# deneme.net
KiCad netlist of a schematic drawn in EAGLE
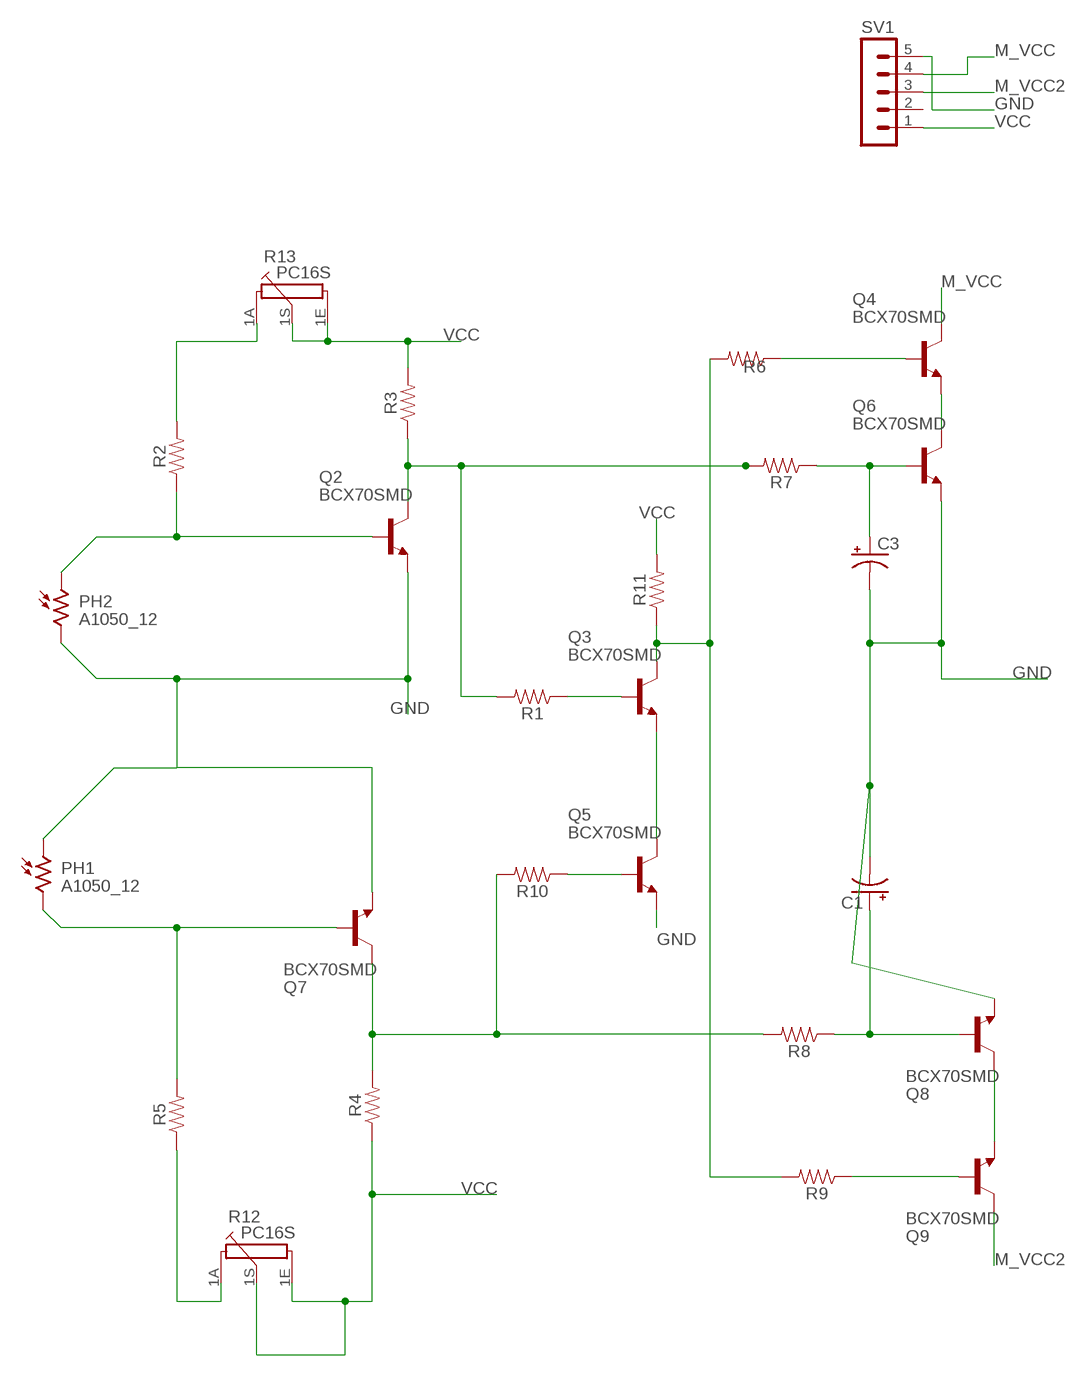
[diagram p0: schematic, sheet 1]

(export (version "E")
  (design (tool "Eeschema 10.0.6"))
  (components
    (comp (ref "C1")
      (value "CPOL-USUD-6,3X7,7")
      (footprint "eagle-import:UD-6,3X7,7_NICHICON")
      (libsource (lib "eagle-import") (part "CPOL-USUD-6,3X7,7"))
    )
    (comp (ref "C3")
      (value "CPOL-USUD-6,3X7,7")
      (footprint "eagle-import:UD-6,3X7,7_NICHICON")
      (libsource (lib "eagle-import") (part "CPOL-USUD-6,3X7,7"))
    )
    (comp (ref "PH1")
      (value "A1050_12")
      (footprint "eagle-import:T0-46-A10XX")
      (libsource (lib "eagle-import") (part "A1050_12"))
    )
    (comp (ref "PH2")
      (value "A1050_12")
      (footprint "eagle-import:T0-46-A10XX")
      (libsource (lib "eagle-import") (part "A1050_12"))
    )
    (comp (ref "Q2")
      (value "BCX70SMD")
      (footprint "eagle-import:SOT23")
      (libsource (lib "eagle-import") (part "BCX70SMD"))
    )
    (comp (ref "Q3")
      (value "BCX70SMD")
      (footprint "eagle-import:SOT23")
      (libsource (lib "eagle-import") (part "BCX70SMD"))
    )
    (comp (ref "Q4")
      (value "BCX70SMD")
      (footprint "eagle-import:SOT23")
      (libsource (lib "eagle-import") (part "BCX70SMD"))
    )
    (comp (ref "Q5")
      (value "BCX70SMD")
      (footprint "eagle-import:SOT23")
      (libsource (lib "eagle-import") (part "BCX70SMD"))
    )
    (comp (ref "Q6")
      (value "BCX70SMD")
      (footprint "eagle-import:SOT23")
      (libsource (lib "eagle-import") (part "BCX70SMD"))
    )
    (comp (ref "Q7")
      (value "BCX70SMD")
      (footprint "eagle-import:SOT23")
      (libsource (lib "eagle-import") (part "BCX70SMD"))
    )
    (comp (ref "Q8")
      (value "BCX70SMD")
      (footprint "eagle-import:SOT23")
      (libsource (lib "eagle-import") (part "BCX70SMD"))
    )
    (comp (ref "Q9")
      (value "BCX70SMD")
      (footprint "eagle-import:SOT23")
      (libsource (lib "eagle-import") (part "BCX70SMD"))
    )
    (comp (ref "R1")
      (value "RESISTOR0805")
      (footprint "eagle-import:0805")
      (libsource (lib "eagle-import") (part "RESISTOR0805"))
    )
    (comp (ref "R2")
      (value "RESISTOR0805")
      (footprint "eagle-import:0805")
      (libsource (lib "eagle-import") (part "RESISTOR0805"))
    )
    (comp (ref "R3")
      (value "RESISTOR0805")
      (footprint "eagle-import:0805")
      (libsource (lib "eagle-import") (part "RESISTOR0805"))
    )
    (comp (ref "R4")
      (value "RESISTOR0805")
      (footprint "eagle-import:0805")
      (libsource (lib "eagle-import") (part "RESISTOR0805"))
    )
    (comp (ref "R5")
      (value "RESISTOR0805")
      (footprint "eagle-import:0805")
      (libsource (lib "eagle-import") (part "RESISTOR0805"))
    )
    (comp (ref "R6")
      (value "RESISTOR0805")
      (footprint "eagle-import:0805")
      (libsource (lib "eagle-import") (part "RESISTOR0805"))
    )
    (comp (ref "R7")
      (value "RESISTOR0805")
      (footprint "eagle-import:0805")
      (libsource (lib "eagle-import") (part "RESISTOR0805"))
    )
    (comp (ref "R8")
      (value "RESISTOR0805")
      (footprint "eagle-import:0805")
      (libsource (lib "eagle-import") (part "RESISTOR0805"))
    )
    (comp (ref "R9")
      (value "RESISTOR0805")
      (footprint "eagle-import:0805")
      (libsource (lib "eagle-import") (part "RESISTOR0805"))
    )
    (comp (ref "R10")
      (value "RESISTOR0805")
      (footprint "eagle-import:0805")
      (libsource (lib "eagle-import") (part "RESISTOR0805"))
    )
    (comp (ref "R11")
      (value "RESISTOR0805")
      (footprint "eagle-import:0805")
      (libsource (lib "eagle-import") (part "RESISTOR0805"))
    )
    (comp (ref "R12")
      (value "PC16S")
      (footprint "eagle-import:PC16S")
      (libsource (lib "eagle-import") (part "PC16S"))
    )
    (comp (ref "R13")
      (value "PC16S")
      (footprint "eagle-import:PC16S")
      (libsource (lib "eagle-import") (part "PC16S"))
    )
    (comp (ref "SV1")
      (value "MA05-1")
      (footprint "eagle-import:MA05-1")
      (libsource (lib "eagle-import") (part "MA05-1"))
    )
  )
  (nets
    (net (code "1") (name "/GND") (class "Default")
      (node (ref "C1") (pin "-") (pinfunction "-_-") (pintype "passive"))
      (node (ref "C3") (pin "-") (pinfunction "-_-") (pintype "passive"))
      (node (ref "PH1") (pin "1") (pinfunction "1_1") (pintype "passive"))
      (node (ref "PH2") (pin "2") (pinfunction "2_2") (pintype "passive"))
      (node (ref "Q2") (pin "2") (pinfunction "E_2") (pintype "passive"))
      (node (ref "Q5") (pin "2") (pinfunction "E_2") (pintype "passive"))
      (node (ref "Q6") (pin "2") (pinfunction "E_2") (pintype "passive"))
      (node (ref "Q7") (pin "2") (pinfunction "E_2") (pintype "passive"))
      (node (ref "Q8") (pin "2") (pinfunction "E_2") (pintype "passive"))
      (node (ref "SV1") (pin "5") (pinfunction "5_5") (pintype "passive"))
    )
    (net (code "2") (name "/M_VCC") (class "Default")
      (node (ref "Q4") (pin "3") (pinfunction "C_3") (pintype "passive"))
      (node (ref "SV1") (pin "4") (pinfunction "4_4") (pintype "passive"))
    )
    (net (code "3") (name "/M_VCC2") (class "Default")
      (node (ref "Q9") (pin "3") (pinfunction "C_3") (pintype "passive"))
      (node (ref "SV1") (pin "3") (pinfunction "3_3") (pintype "passive"))
    )
    (net (code "4") (name "/VCC") (class "Default")
      (node (ref "R11") (pin "2") (pinfunction "2_2") (pintype "passive"))
      (node (ref "R12") (pin "1E") (pinfunction "1E_1E") (pintype "passive"))
      (node (ref "R12") (pin "1S") (pinfunction "1S_1S") (pintype "passive"))
      (node (ref "R13") (pin "1E") (pinfunction "1E_1E") (pintype "passive"))
      (node (ref "R13") (pin "1S") (pinfunction "1S_1S") (pintype "passive"))
      (node (ref "R3") (pin "2") (pinfunction "2_2") (pintype "passive"))
      (node (ref "R4") (pin "1") (pinfunction "1_1") (pintype "passive"))
      (node (ref "SV1") (pin "1") (pinfunction "1_1") (pintype "passive"))
    )
    (net (code "5") (name "Net-(Q2-B)") (class "Default")
      (node (ref "PH2") (pin "1") (pinfunction "1_1") (pintype "passive"))
      (node (ref "Q2") (pin "1") (pinfunction "B_1") (pintype "passive"))
      (node (ref "R2") (pin "1") (pinfunction "1_1") (pintype "passive"))
    )
    (net (code "6") (name "Net-(Q2-C)") (class "Default")
      (node (ref "Q2") (pin "3") (pinfunction "C_3") (pintype "passive"))
      (node (ref "R1") (pin "2") (pinfunction "2_2") (pintype "passive"))
      (node (ref "R3") (pin "1") (pinfunction "1_1") (pintype "passive"))
      (node (ref "R7") (pin "2") (pinfunction "2_2") (pintype "passive"))
    )
    (net (code "7") (name "Net-(Q3-B)") (class "Default")
      (node (ref "Q3") (pin "1") (pinfunction "B_1") (pintype "passive"))
      (node (ref "R1") (pin "1") (pinfunction "1_1") (pintype "passive"))
    )
    (net (code "8") (name "Net-(Q3-C)") (class "Default")
      (node (ref "Q3") (pin "3") (pinfunction "C_3") (pintype "passive"))
      (node (ref "R11") (pin "1") (pinfunction "1_1") (pintype "passive"))
      (node (ref "R6") (pin "2") (pinfunction "2_2") (pintype "passive"))
      (node (ref "R9") (pin "2") (pinfunction "2_2") (pintype "passive"))
    )
    (net (code "9") (name "Net-(Q3-E)") (class "Default")
      (node (ref "Q3") (pin "2") (pinfunction "E_2") (pintype "passive"))
      (node (ref "Q5") (pin "3") (pinfunction "C_3") (pintype "passive"))
    )
    (net (code "10") (name "Net-(Q4-B)") (class "Default")
      (node (ref "Q4") (pin "1") (pinfunction "B_1") (pintype "passive"))
      (node (ref "R6") (pin "1") (pinfunction "1_1") (pintype "passive"))
    )
    (net (code "11") (name "Net-(Q4-E)") (class "Default")
      (node (ref "Q4") (pin "2") (pinfunction "E_2") (pintype "passive"))
      (node (ref "Q6") (pin "3") (pinfunction "C_3") (pintype "passive"))
    )
    (net (code "12") (name "Net-(Q5-B)") (class "Default")
      (node (ref "Q5") (pin "1") (pinfunction "B_1") (pintype "passive"))
      (node (ref "R10") (pin "1") (pinfunction "1_1") (pintype "passive"))
    )
    (net (code "13") (name "Net-(Q6-B)") (class "Default")
      (node (ref "C3") (pin "+") (pinfunction "+_+") (pintype "passive"))
      (node (ref "Q6") (pin "1") (pinfunction "B_1") (pintype "passive"))
      (node (ref "R7") (pin "1") (pinfunction "1_1") (pintype "passive"))
    )
    (net (code "14") (name "Net-(Q7-B)") (class "Default")
      (node (ref "PH1") (pin "2") (pinfunction "2_2") (pintype "passive"))
      (node (ref "Q7") (pin "1") (pinfunction "B_1") (pintype "passive"))
      (node (ref "R5") (pin "2") (pinfunction "2_2") (pintype "passive"))
    )
    (net (code "15") (name "Net-(Q7-C)") (class "Default")
      (node (ref "Q7") (pin "3") (pinfunction "C_3") (pintype "passive"))
      (node (ref "R10") (pin "2") (pinfunction "2_2") (pintype "passive"))
      (node (ref "R4") (pin "2") (pinfunction "2_2") (pintype "passive"))
      (node (ref "R8") (pin "2") (pinfunction "2_2") (pintype "passive"))
    )
    (net (code "16") (name "Net-(Q8-B)") (class "Default")
      (node (ref "C1") (pin "+") (pinfunction "+_+") (pintype "passive"))
      (node (ref "Q8") (pin "1") (pinfunction "B_1") (pintype "passive"))
      (node (ref "R8") (pin "1") (pinfunction "1_1") (pintype "passive"))
    )
    (net (code "17") (name "Net-(Q8-C)") (class "Default")
      (node (ref "Q8") (pin "3") (pinfunction "C_3") (pintype "passive"))
      (node (ref "Q9") (pin "2") (pinfunction "E_2") (pintype "passive"))
    )
    (net (code "18") (name "Net-(Q9-B)") (class "Default")
      (node (ref "Q9") (pin "1") (pinfunction "B_1") (pintype "passive"))
      (node (ref "R9") (pin "1") (pinfunction "1_1") (pintype "passive"))
    )
    (net (code "19") (name "Net-(R12-Pad1A)") (class "Default")
      (node (ref "R12") (pin "1A") (pinfunction "1A_1A") (pintype "passive"))
      (node (ref "R5") (pin "1") (pinfunction "1_1") (pintype "passive"))
    )
    (net (code "20") (name "Net-(R13-Pad1A)") (class "Default")
      (node (ref "R13") (pin "1A") (pinfunction "1A_1A") (pintype "passive"))
      (node (ref "R2") (pin "2") (pinfunction "2_2") (pintype "passive"))
    )
    (net (code "21") (name "unconnected-(SV1-Pad2)") (class "Default")
      (node (ref "SV1") (pin "2") (pinfunction "2_2") (pintype "passive"))
    )
  )
)
